# H3_SDCard.net
KiCad netlist of a schematic drawn in Altium Designer
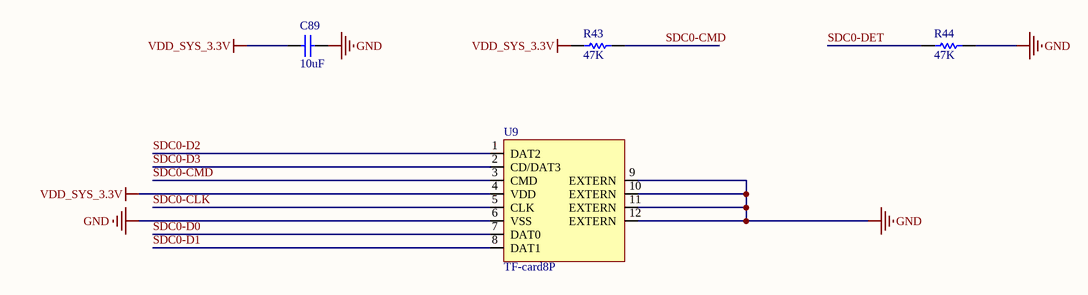
[diagram p0: H3_SDCard.SchDoc]

(export (version "E")
  (design (tool "Eeschema 10.0.6"))
  (components
    (comp (ref "C89")
      (value "10uF")
      (footprint "H3_Core:C0402")
      (description "电容")
      (fields (field (name "PUBLISHER") "Altium Limited"))
      (libsource (lib "Devices") (part "C0603"))
    )
    (comp (ref "R43")
      (value "47K")
      (footprint "H3_Core:R0402")
      (description "电阻")
      (fields (field (name "PUBLISHER") "Altium Limited"))
      (libsource (lib "Devices") (part "RES0402"))
    )
    (comp (ref "R44")
      (value "47K")
      (footprint "H3_Core:R0402")
      (description "电阻")
      (fields (field (name "PUBLISHER") "Altium Limited"))
      (libsource (lib "Devices") (part "RES0402"))
    )
    (comp (ref "U9")
      (value "TF-card8P")
      (footprint "MINI-copter:TF-8P - duplicate")
      (libsource (lib "MINI-copter") (part "TF-card8P"))
    )
  )
  (nets
    (net (code "1") (name "/SDC0-CLK") (class "Default")
      (node (ref "U9") (pin "5") (pinfunction "CLK_5") (pintype "passive"))
    )
    (net (code "2") (name "/SDC0-CMD") (class "Default")
      (node (ref "R43") (pin "1") (pinfunction "1_1") (pintype "passive"))
      (node (ref "U9") (pin "3") (pinfunction "CMD_3") (pintype "passive"))
    )
    (net (code "3") (name "/SDC0-D0") (class "Default")
      (node (ref "U9") (pin "7") (pinfunction "DAT0_7") (pintype "passive"))
    )
    (net (code "4") (name "/SDC0-D1") (class "Default")
      (node (ref "U9") (pin "8") (pinfunction "DAT1_8") (pintype "passive"))
    )
    (net (code "5") (name "/SDC0-D2") (class "Default")
      (node (ref "U9") (pin "1") (pinfunction "DAT2_1") (pintype "passive"))
    )
    (net (code "6") (name "/SDC0-D3") (class "Default")
      (node (ref "U9") (pin "2") (pinfunction "CD/DAT3_2") (pintype "passive"))
    )
    (net (code "7") (name "/SDC0-DET") (class "Default")
      (node (ref "R44") (pin "2") (pinfunction "2_2") (pintype "passive"))
    )
    (net (code "8") (name "GND") (class "Default")
      (node (ref "C89") (pin "1") (pinfunction "1_1") (pintype "passive"))
      (node (ref "R44") (pin "1") (pinfunction "1_1") (pintype "passive"))
      (node (ref "U9") (pin "10") (pinfunction "EXTERN_10") (pintype "passive"))
      (node (ref "U9") (pin "11") (pinfunction "EXTERN_11") (pintype "passive"))
      (node (ref "U9") (pin "12") (pinfunction "EXTERN_12") (pintype "passive"))
      (node (ref "U9") (pin "6") (pinfunction "VSS_6") (pintype "passive"))
      (node (ref "U9") (pin "9") (pinfunction "EXTERN_9") (pintype "passive"))
    )
    (net (code "9") (name "VDD_SYS_3.3V") (class "Default")
      (node (ref "C89") (pin "2") (pinfunction "2_2") (pintype "passive"))
      (node (ref "R43") (pin "2") (pinfunction "2_2") (pintype "passive"))
      (node (ref "U9") (pin "4") (pinfunction "VDD_4") (pintype "passive"))
    )
  )
)
